# Sche.net
KiCad netlist of a schematic drawn in Altium Designer
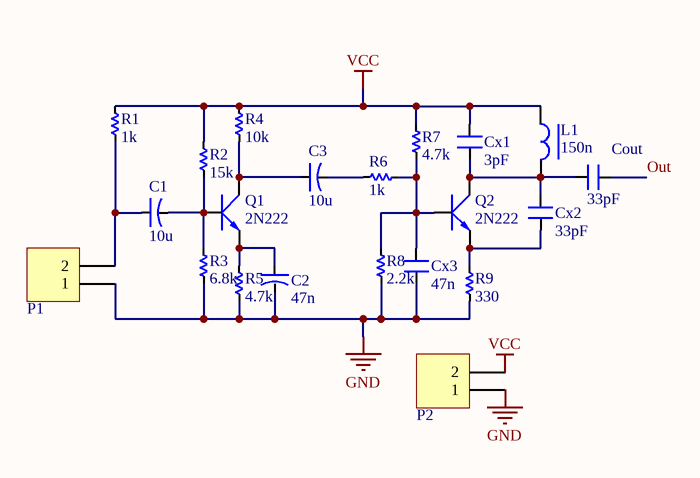
[diagram p0: Sche.SchDoc]

(export (version "E")
  (design (tool "Eeschema 10.0.6"))
  (components
    (comp (ref "C1")
      (value "10u")
      (footprint "CA-ALU-2.54")
      (description "Capacitor (Semiconductor SIM Model)")
      (fields (field (name "PUBLISHER") "Altium Limited"))
      (libsource (lib "LIBRARY") (part "CN-ALU-DIP"))
    )
    (comp (ref "C2")
      (value "47n")
      (footprint "CA-ALU-2.54")
      (description "Capacitor (Semiconductor SIM Model)")
      (fields (field (name "PUBLISHER") "Altium Limited"))
      (libsource (lib "LIBRARY") (part "CN-ALU-DIP"))
    )
    (comp (ref "C3")
      (value "10u")
      (footprint "CA-ALU-2.54")
      (description "Capacitor (Semiconductor SIM Model)")
      (fields (field (name "PUBLISHER") "Altium Limited"))
      (libsource (lib "LIBRARY") (part "CN-ALU-DIP"))
    )
    (comp (ref "Cout") (value "33pF") (footprint "CN-SMD-0805") (libsource (lib "LIBRARY") (part "CN")))
    (comp (ref "Cx1") (value "3pF") (footprint "CN-SMD-0805") (libsource (lib "LIBRARY") (part "CN")))
    (comp (ref "Cx2") (value "33pF") (footprint "CN-SMD-0805") (libsource (lib "LIBRARY") (part "CN")))
    (comp (ref "Cx3") (value "47n") (footprint "CN-SMD-0805") (libsource (lib "LIBRARY") (part "CN")))
    (comp (ref "L1")
      (value "150n")
      (footprint "RES-1/8W-SMALL")
      (description "Inductor")
      (libsource (lib "LIBRARY") (part "L-DIP-1"))
    )
    (comp (ref "P1")
      (value "Domino 2")
      (footprint "DOMINO 2- 5mm")
      (description "Domino, 2-Pin")
      (fields (field (name "PUBLISHER") "Altium Limited"))
      (libsource (lib "PIF_Library") (part "Domino 2"))
    )
    (comp (ref "P2")
      (value "Domino 2")
      (footprint "DOMINO 2- 5mm")
      (description "Domino, 2-Pin")
      (fields (field (name "PUBLISHER") "Altium Limited"))
      (libsource (lib "PIF_Library") (part "Domino 2"))
    )
    (comp (ref "Q1")
      (value "2N222")
      (footprint "TO92-123")
      (description "NPN 600mW, ECB")
      (libsource (lib "LIBRARY") (part "2N222"))
    )
    (comp (ref "Q2")
      (value "2N222")
      (footprint "TO92-123")
      (description "NPN 600mW, ECB")
      (libsource (lib "LIBRARY") (part "2N222"))
    )
    (comp (ref "R1")
      (value "1k")
      (footprint "RES-SMD-0805")
      (description "Resistor")
      (fields
        (field (name "MANUFACTURER") "Generic Components")
        (field (name "PUBLISHER") "Altium Hobart Technology Centre")
      )
      (libsource (lib "LIBRARY") (part "Res-SMD"))
    )
    (comp (ref "R2")
      (value "15k")
      (footprint "RES-SMD-0805")
      (description "Resistor")
      (fields
        (field (name "MANUFACTURER") "Generic Components")
        (field (name "PUBLISHER") "Altium Hobart Technology Centre")
      )
      (libsource (lib "LIBRARY") (part "Res-SMD"))
    )
    (comp (ref "R3")
      (value "6.8k")
      (footprint "RES-SMD-0805")
      (description "Resistor")
      (fields
        (field (name "MANUFACTURER") "Generic Components")
        (field (name "PUBLISHER") "Altium Hobart Technology Centre")
      )
      (libsource (lib "LIBRARY") (part "Res-SMD"))
    )
    (comp (ref "R4")
      (value "10k")
      (footprint "RES-SMD-0805")
      (description "Resistor")
      (fields
        (field (name "MANUFACTURER") "Generic Components")
        (field (name "PUBLISHER") "Altium Hobart Technology Centre")
      )
      (libsource (lib "LIBRARY") (part "Res-SMD"))
    )
    (comp (ref "R5")
      (value "4.7k")
      (footprint "RES-SMD-0805")
      (description "Resistor")
      (fields
        (field (name "MANUFACTURER") "Generic Components")
        (field (name "PUBLISHER") "Altium Hobart Technology Centre")
      )
      (libsource (lib "LIBRARY") (part "Res-SMD"))
    )
    (comp (ref "R6")
      (value "1k")
      (footprint "RES-SMD-0805")
      (description "Resistor")
      (fields
        (field (name "MANUFACTURER") "Generic Components")
        (field (name "PUBLISHER") "Altium Hobart Technology Centre")
      )
      (libsource (lib "LIBRARY") (part "Res-SMD"))
    )
    (comp (ref "R7")
      (value "4.7k")
      (footprint "RES-SMD-0805")
      (description "Resistor")
      (fields
        (field (name "MANUFACTURER") "Generic Components")
        (field (name "PUBLISHER") "Altium Hobart Technology Centre")
      )
      (libsource (lib "LIBRARY") (part "Res-SMD"))
    )
    (comp (ref "R8")
      (value "2.2k")
      (footprint "RES-SMD-0805")
      (description "Resistor")
      (fields
        (field (name "MANUFACTURER") "Generic Components")
        (field (name "PUBLISHER") "Altium Hobart Technology Centre")
      )
      (libsource (lib "LIBRARY") (part "Res-SMD"))
    )
    (comp (ref "R9")
      (value "330")
      (footprint "RES-SMD-0805")
      (description "Resistor")
      (fields
        (field (name "MANUFACTURER") "Generic Components")
        (field (name "PUBLISHER") "Altium Hobart Technology Centre")
      )
      (libsource (lib "LIBRARY") (part "Res-SMD"))
    )
  )
  (nets
    (net (code "1") (name "/Out") (class "Default")
      (node (ref "Cout") (pin "1") (pinfunction "1_1") (pintype "passive"))
    )
    (net (code "2") (name "GND") (class "Default")
      (node (ref "C2") (pin "2") (pinfunction "2_2") (pintype "passive"))
      (node (ref "Cx3") (pin "1") (pinfunction "1_1") (pintype "passive"))
      (node (ref "P1") (pin "1") (pinfunction "1_1") (pintype "passive"))
      (node (ref "P2") (pin "1") (pinfunction "1_1") (pintype "passive"))
      (node (ref "R3") (pin "2") (pinfunction "2_2") (pintype "passive"))
      (node (ref "R5") (pin "2") (pinfunction "2_2") (pintype "passive"))
      (node (ref "R8") (pin "2") (pinfunction "2_2") (pintype "passive"))
      (node (ref "R9") (pin "2") (pinfunction "2_2") (pintype "passive"))
    )
    (net (code "3") (name "Net-(C1-Pad1)") (class "Default")
      (node (ref "C1") (pin "1") (pinfunction "1_1") (pintype "passive"))
      (node (ref "P1") (pin "2") (pinfunction "2_2") (pintype "passive"))
      (node (ref "R1") (pin "2") (pinfunction "2_2") (pintype "passive"))
    )
    (net (code "4") (name "Net-(C3-Pad2)") (class "Default")
      (node (ref "C3") (pin "2") (pinfunction "2_2") (pintype "passive"))
      (node (ref "R6") (pin "1") (pinfunction "1_1") (pintype "passive"))
    )
    (net (code "5") (name "Net-(Q1-B)") (class "Default")
      (node (ref "C1") (pin "2") (pinfunction "2_2") (pintype "passive"))
      (node (ref "Q1") (pin "2") (pinfunction "B_2") (pintype "passive"))
      (node (ref "R2") (pin "2") (pinfunction "2_2") (pintype "passive"))
      (node (ref "R3") (pin "1") (pinfunction "1_1") (pintype "passive"))
    )
    (net (code "6") (name "Net-(Q1-C)") (class "Default")
      (node (ref "C3") (pin "1") (pinfunction "1_1") (pintype "passive"))
      (node (ref "Q1") (pin "3") (pinfunction "C_3") (pintype "passive"))
      (node (ref "R4") (pin "2") (pinfunction "2_2") (pintype "passive"))
    )
    (net (code "7") (name "Net-(Q1-E)") (class "Default")
      (node (ref "C2") (pin "1") (pinfunction "1_1") (pintype "passive"))
      (node (ref "Q1") (pin "1") (pinfunction "E_1") (pintype "passive"))
      (node (ref "R5") (pin "1") (pinfunction "1_1") (pintype "passive"))
    )
    (net (code "8") (name "Net-(Q2-B)") (class "Default")
      (node (ref "Cx3") (pin "2") (pinfunction "2_2") (pintype "passive"))
      (node (ref "Q2") (pin "2") (pinfunction "B_2") (pintype "passive"))
      (node (ref "R6") (pin "2") (pinfunction "2_2") (pintype "passive"))
      (node (ref "R7") (pin "2") (pinfunction "2_2") (pintype "passive"))
      (node (ref "R8") (pin "1") (pinfunction "1_1") (pintype "passive"))
    )
    (net (code "9") (name "Net-(Q2-C)") (class "Default")
      (node (ref "Cout") (pin "2") (pinfunction "2_2") (pintype "passive"))
      (node (ref "Cx1") (pin "1") (pinfunction "1_1") (pintype "passive"))
      (node (ref "Cx2") (pin "2") (pinfunction "2_2") (pintype "passive"))
      (node (ref "L1") (pin "2") (pinfunction "2_2") (pintype "passive"))
      (node (ref "Q2") (pin "3") (pinfunction "C_3") (pintype "passive"))
    )
    (net (code "10") (name "Net-(Q2-E)") (class "Default")
      (node (ref "Cx2") (pin "1") (pinfunction "1_1") (pintype "passive"))
      (node (ref "Q2") (pin "1") (pinfunction "E_1") (pintype "passive"))
      (node (ref "R9") (pin "1") (pinfunction "1_1") (pintype "passive"))
    )
    (net (code "11") (name "VCC") (class "Default")
      (node (ref "Cx1") (pin "2") (pinfunction "2_2") (pintype "passive"))
      (node (ref "L1") (pin "1") (pinfunction "1_1") (pintype "passive"))
      (node (ref "P2") (pin "2") (pinfunction "2_2") (pintype "passive"))
      (node (ref "R1") (pin "1") (pinfunction "1_1") (pintype "passive"))
      (node (ref "R2") (pin "1") (pinfunction "1_1") (pintype "passive"))
      (node (ref "R4") (pin "1") (pinfunction "1_1") (pintype "passive"))
      (node (ref "R7") (pin "1") (pinfunction "1_1") (pintype "passive"))
    )
  )
)
